# working.net
KiCad netlist of a schematic drawn in EAGLE
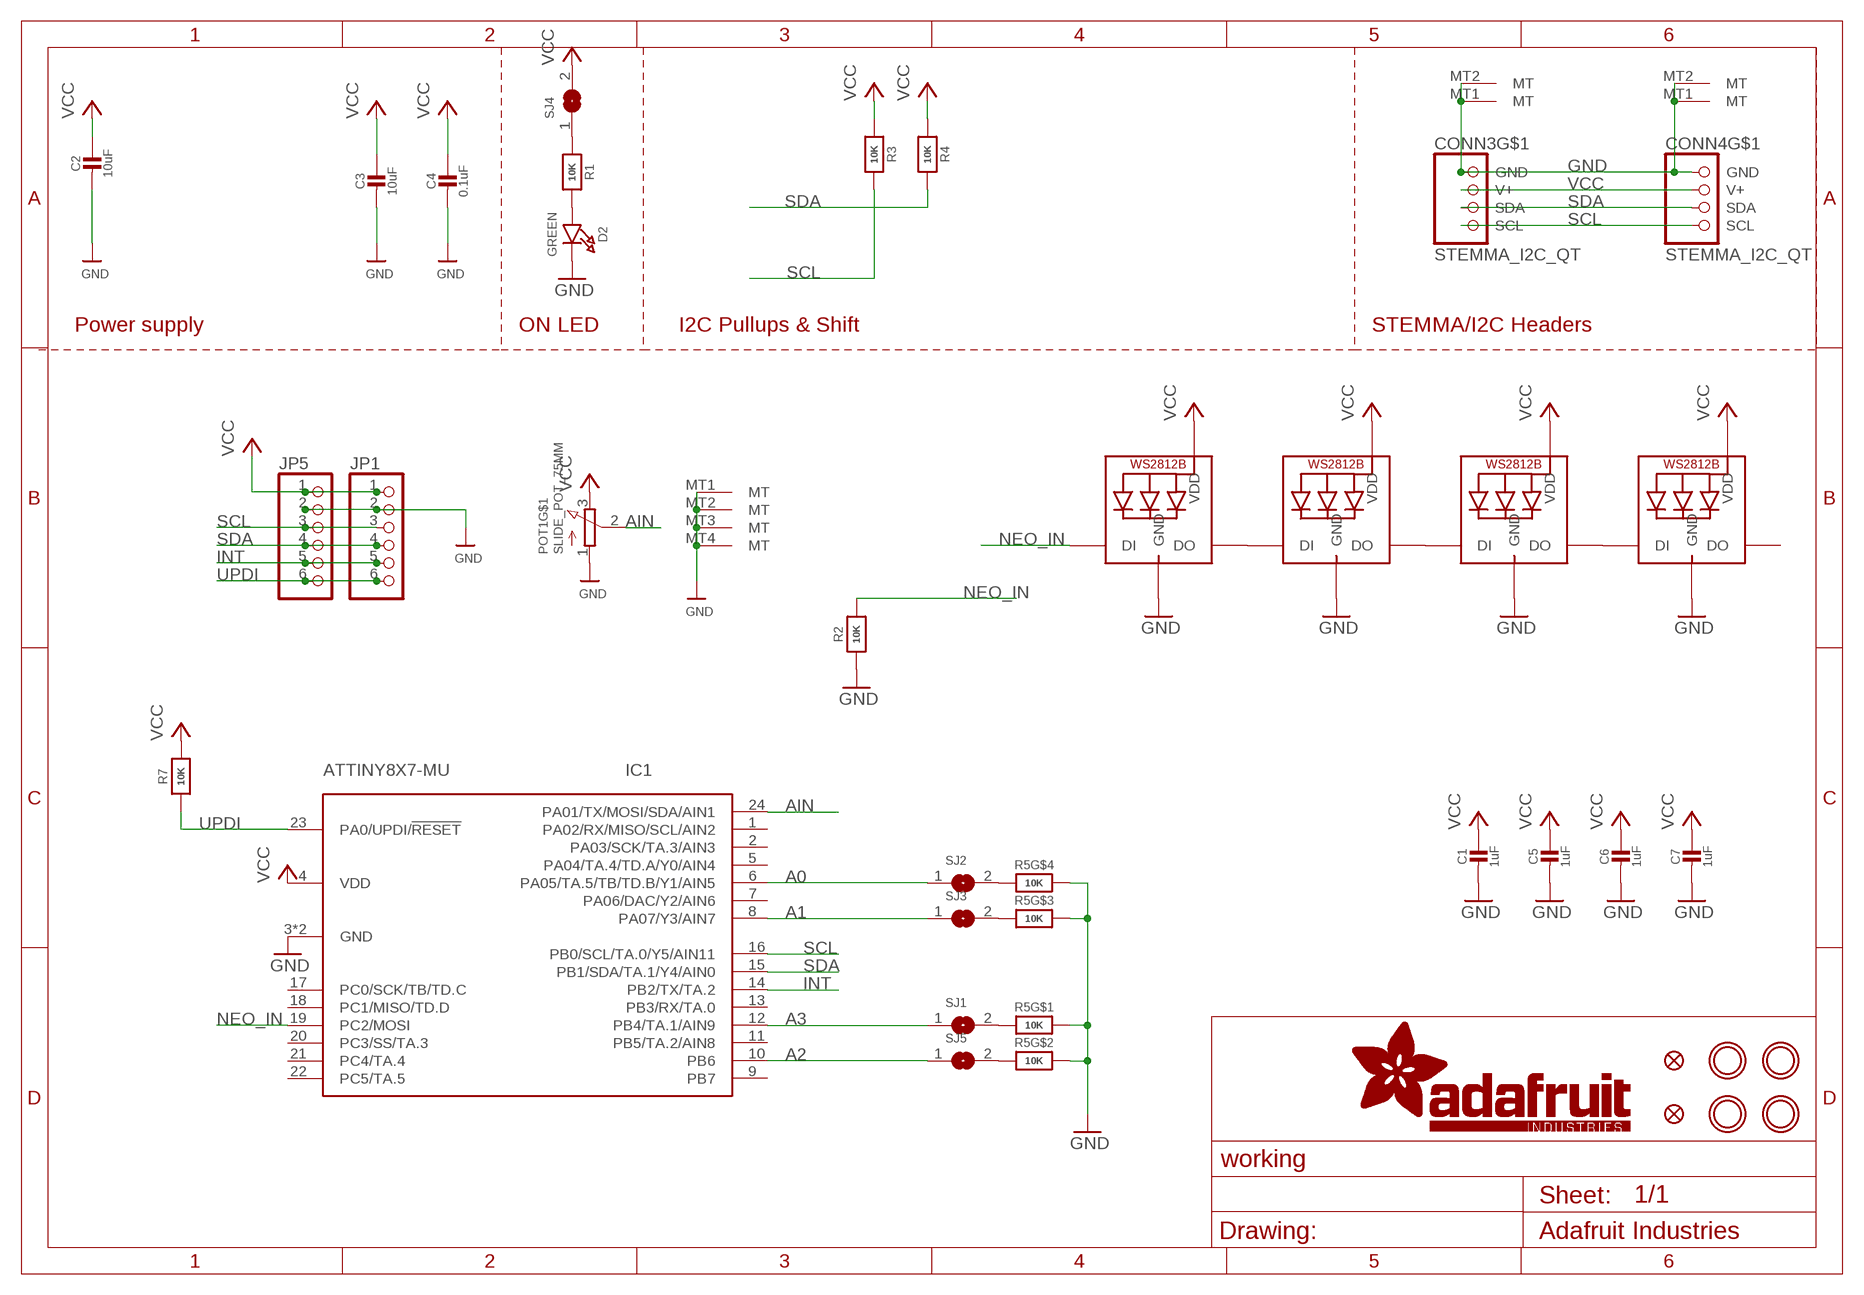
[diagram p0: schematic, sheet 1]

(export (version "E")
  (design (tool "Eeschema 10.0.6"))
  (components
    (comp (ref "C1")
      (value "1uF")
      (footprint "eagle-import:0603-NO")
      (libsource (lib "eagle-import") (part "CAP_CERAMIC0603_NO"))
    )
    (comp (ref "C2")
      (value "10uF")
      (footprint "eagle-import:0805-NO")
      (libsource (lib "eagle-import") (part "CAP_CERAMIC0805-NOOUTLINE"))
    )
    (comp (ref "C3")
      (value "10uF")
      (footprint "eagle-import:0805-NO")
      (libsource (lib "eagle-import") (part "CAP_CERAMIC0805-NOOUTLINE"))
    )
    (comp (ref "C4")
      (value "0.1uF")
      (footprint "eagle-import:0603-NO")
      (libsource (lib "eagle-import") (part "CAP_CERAMIC0603_NO"))
    )
    (comp (ref "C5")
      (value "1uF")
      (footprint "eagle-import:0603-NO")
      (libsource (lib "eagle-import") (part "CAP_CERAMIC0603_NO"))
    )
    (comp (ref "C6")
      (value "1uF")
      (footprint "eagle-import:0603-NO")
      (libsource (lib "eagle-import") (part "CAP_CERAMIC0603_NO"))
    )
    (comp (ref "C7")
      (value "1uF")
      (footprint "eagle-import:0603-NO")
      (libsource (lib "eagle-import") (part "CAP_CERAMIC0603_NO"))
    )
    (comp (ref "CONN3")
      (value "STEMMA_I2C_QT")
      (footprint "eagle-import:JST_SH4")
      (libsource (lib "eagle-import") (part "STEMMA_I2C_QT"))
    )
    (comp (ref "CONN4")
      (value "STEMMA_I2C_QT")
      (footprint "eagle-import:JST_SH4")
      (libsource (lib "eagle-import") (part "STEMMA_I2C_QT"))
    )
    (comp (ref "D2")
      (value "GREEN")
      (footprint "eagle-import:CHIPLED_0603_NOOUTLINE")
      (libsource (lib "eagle-import") (part "LED0603_NOOUTLINE"))
    )
    (comp (ref "FID1")
      (value "FIDUCIAL_1MM")
      (footprint "eagle-import:FIDUCIAL_1MM")
      (libsource (lib "eagle-import") (part "FIDUCIAL_1MM"))
    )
    (comp (ref "FID2")
      (value "FIDUCIAL_1MM")
      (footprint "eagle-import:FIDUCIAL_1MM")
      (libsource (lib "eagle-import") (part "FIDUCIAL_1MM"))
    )
    (comp (ref "IC1")
      (value "ATTINY8X7-MU")
      (footprint "eagle-import:QFN24_4MM")
      (libsource (lib "eagle-import") (part "ATTINY8X7-MU"))
    )
    (comp (ref "JP1")
      (value "HEADER-1X670MIL")
      (footprint "eagle-import:1X06_ROUND_70")
      (libsource (lib "eagle-import") (part "HEADER-1X670MIL"))
    )
    (comp (ref "JP5")
      (value "HEADER-1X670MIL")
      (footprint "eagle-import:1X06_ROUND_70")
      (libsource (lib "eagle-import") (part "HEADER-1X670MIL"))
    )
    (comp (ref "LED1")
      (value "WS2812B_SK6812E")
      (footprint "eagle-import:NEO3535_REVERSE")
      (libsource (lib "eagle-import") (part "WS2812B_SK6812E"))
    )
    (comp (ref "LED2")
      (value "WS2812B_SK6812E")
      (footprint "eagle-import:NEO3535_REVERSE")
      (libsource (lib "eagle-import") (part "WS2812B_SK6812E"))
    )
    (comp (ref "LED3")
      (value "WS2812B_SK6812E")
      (footprint "eagle-import:NEO3535_REVERSE")
      (libsource (lib "eagle-import") (part "WS2812B_SK6812E"))
    )
    (comp (ref "LED4")
      (value "WS2812B_SK6812E")
      (footprint "eagle-import:NEO3535_REVERSE")
      (libsource (lib "eagle-import") (part "WS2812B_SK6812E"))
    )
    (comp (ref "POT1")
      (value "SLIDE_POT_75MM")
      (footprint "eagle-import:SLIDE_POT_75MM")
      (libsource (lib "eagle-import") (part "SLIDE_POT_75MM"))
    )
    (comp (ref "R1")
      (value "10K")
      (footprint "eagle-import:0603-NO")
      (libsource (lib "eagle-import") (part "RESISTOR_0603_NOOUT"))
    )
    (comp (ref "R2")
      (value "10K")
      (footprint "eagle-import:0603-NO")
      (libsource (lib "eagle-import") (part "RESISTOR_0603_NOOUT"))
    )
    (comp (ref "R3")
      (value "10K")
      (footprint "eagle-import:0603-NO")
      (libsource (lib "eagle-import") (part "RESISTOR_0603_NOOUT"))
    )
    (comp (ref "R4")
      (value "10K")
      (footprint "eagle-import:0603-NO")
      (libsource (lib "eagle-import") (part "RESISTOR_0603_NOOUT"))
    )
    (comp (ref "R5")
      (value "10K")
      (footprint "eagle-import:RESPACK_4X0603")
      (libsource (lib "eagle-import") (part "RESISTOR_4PACK"))
    )
    (comp (ref "R7")
      (value "10K")
      (footprint "eagle-import:0603-NO")
      (libsource (lib "eagle-import") (part "RESISTOR_0603_NOOUT"))
    )
    (comp (ref "SJ1")
      (value "SOLDERJUMPERCLOSED")
      (footprint "eagle-import:SOLDERJUMPER_CLOSEDWIRE")
      (libsource (lib "eagle-import") (part "SOLDERJUMPERCLOSED"))
    )
    (comp (ref "SJ2")
      (value "SOLDERJUMPERCLOSED")
      (footprint "eagle-import:SOLDERJUMPER_CLOSEDWIRE")
      (libsource (lib "eagle-import") (part "SOLDERJUMPERCLOSED"))
    )
    (comp (ref "SJ3")
      (value "SOLDERJUMPERCLOSED")
      (footprint "eagle-import:SOLDERJUMPER_CLOSEDWIRE")
      (libsource (lib "eagle-import") (part "SOLDERJUMPERCLOSED"))
    )
    (comp (ref "SJ4")
      (value "SOLDERJUMPERCLOSED")
      (footprint "eagle-import:SOLDERJUMPER_CLOSEDWIRE")
      (libsource (lib "eagle-import") (part "SOLDERJUMPERCLOSED"))
    )
    (comp (ref "SJ5")
      (value "SOLDERJUMPERCLOSED")
      (footprint "eagle-import:SOLDERJUMPER_CLOSEDWIRE")
      (libsource (lib "eagle-import") (part "SOLDERJUMPERCLOSED"))
    )
    (comp (ref "U$3")
      (value "MOUNTINGHOLE2.5")
      (footprint "eagle-import:MOUNTINGHOLE_2.5_PLATED")
      (libsource (lib "eagle-import") (part "MOUNTINGHOLE2.5"))
    )
    (comp (ref "U$17")
      (value "MOUNTINGHOLE2.5")
      (footprint "eagle-import:MOUNTINGHOLE_2.5_PLATED")
      (libsource (lib "eagle-import") (part "MOUNTINGHOLE2.5"))
    )
    (comp (ref "U$19")
      (value "MOUNTINGHOLE2.5")
      (footprint "eagle-import:MOUNTINGHOLE_2.5_PLATED")
      (libsource (lib "eagle-import") (part "MOUNTINGHOLE2.5"))
    )
    (comp (ref "U$21")
      (value "MOUNTINGHOLE2.5")
      (footprint "eagle-import:MOUNTINGHOLE_2.5_PLATED")
      (libsource (lib "eagle-import") (part "MOUNTINGHOLE2.5"))
    )
  )
  (nets
    (net (code "1") (name "/A0") (class "Default")
      (node (ref "IC1") (pin "6") (pinfunction "PA05/TA.5/TB/TD.B/Y1/AIN5_6") (pintype "bidirectional"))
      (node (ref "SJ2") (pin "1") (pinfunction "1_1") (pintype "passive"))
    )
    (net (code "2") (name "/A1") (class "Default")
      (node (ref "IC1") (pin "8") (pinfunction "PA07/Y3/AIN7_8") (pintype "bidirectional"))
      (node (ref "SJ3") (pin "1") (pinfunction "1_1") (pintype "passive"))
    )
    (net (code "3") (name "/A2") (class "Default")
      (node (ref "IC1") (pin "10") (pinfunction "PB6_10") (pintype "bidirectional"))
      (node (ref "SJ5") (pin "1") (pinfunction "1_1") (pintype "passive"))
    )
    (net (code "4") (name "/A3") (class "Default")
      (node (ref "IC1") (pin "12") (pinfunction "PB4/TA.1/AIN9_12") (pintype "bidirectional"))
      (node (ref "SJ1") (pin "1") (pinfunction "1_1") (pintype "passive"))
    )
    (net (code "5") (name "/AIN") (class "Default")
      (node (ref "IC1") (pin "24") (pinfunction "PA01/TX/MOSI/SDA/AIN1_24") (pintype "bidirectional"))
      (node (ref "POT1") (pin "2") (pinfunction "S_2") (pintype "passive"))
    )
    (net (code "6") (name "/INT") (class "Default")
      (node (ref "IC1") (pin "14") (pinfunction "PB2/TX/TA.2_14") (pintype "bidirectional"))
      (node (ref "JP1") (pin "5") (pinfunction "5_5") (pintype "passive"))
      (node (ref "JP5") (pin "5") (pinfunction "5_5") (pintype "passive"))
    )
    (net (code "7") (name "/NEO_IN") (class "Default")
      (node (ref "IC1") (pin "19") (pinfunction "PC2/MOSI_19") (pintype "bidirectional"))
      (node (ref "LED1") (pin "4-DIN") (pinfunction "DI_4-DIN") (pintype "input"))
      (node (ref "R2") (pin "2") (pinfunction "2_2") (pintype "passive"))
    )
    (net (code "8") (name "/SCL") (class "Default")
      (node (ref "CONN3") (pin "4") (pinfunction "SCL_4") (pintype "passive"))
      (node (ref "CONN4") (pin "4") (pinfunction "SCL_4") (pintype "passive"))
      (node (ref "IC1") (pin "16") (pinfunction "PB0/SCL/TA.0/Y5/AIN11_16") (pintype "bidirectional"))
      (node (ref "JP1") (pin "3") (pinfunction "3_3") (pintype "passive"))
      (node (ref "JP5") (pin "3") (pinfunction "3_3") (pintype "passive"))
      (node (ref "R3") (pin "2") (pinfunction "2_2") (pintype "passive"))
    )
    (net (code "9") (name "/SDA") (class "Default")
      (node (ref "CONN3") (pin "3") (pinfunction "SDA_3") (pintype "passive"))
      (node (ref "CONN4") (pin "3") (pinfunction "SDA_3") (pintype "passive"))
      (node (ref "IC1") (pin "15") (pinfunction "PB1/SDA/TA.1/Y4/AIN0_15") (pintype "bidirectional"))
      (node (ref "JP1") (pin "4") (pinfunction "4_4") (pintype "passive"))
      (node (ref "JP5") (pin "4") (pinfunction "4_4") (pintype "passive"))
      (node (ref "R4") (pin "2") (pinfunction "2_2") (pintype "passive"))
    )
    (net (code "10") (name "/UPDI") (class "Default")
      (node (ref "IC1") (pin "23") (pinfunction "PA0/UPDI/~{RESET}_23") (pintype "bidirectional"))
      (node (ref "JP1") (pin "6") (pinfunction "6_6") (pintype "passive"))
      (node (ref "JP5") (pin "6") (pinfunction "6_6") (pintype "passive"))
      (node (ref "R7") (pin "1") (pinfunction "1_1") (pintype "passive"))
    )
    (net (code "11") (name "GND") (class "Default")
      (node (ref "C1") (pin "2") (pinfunction "2_2") (pintype "passive"))
      (node (ref "C2") (pin "2") (pinfunction "2_2") (pintype "passive"))
      (node (ref "C3") (pin "2") (pinfunction "2_2") (pintype "passive"))
      (node (ref "C4") (pin "2") (pinfunction "2_2") (pintype "passive"))
      (node (ref "C5") (pin "2") (pinfunction "2_2") (pintype "passive"))
      (node (ref "C6") (pin "2") (pinfunction "2_2") (pintype "passive"))
      (node (ref "C7") (pin "2") (pinfunction "2_2") (pintype "passive"))
      (node (ref "CONN3") (pin "1") (pinfunction "GND_1") (pintype "passive"))
      (node (ref "CONN3") (pin "MT1") (pinfunction "MT_MT1") (pintype "bidirectional"))
      (node (ref "CONN3") (pin "MT2") (pinfunction "MT_MT2") (pintype "bidirectional"))
      (node (ref "CONN4") (pin "1") (pinfunction "GND_1") (pintype "passive"))
      (node (ref "CONN4") (pin "MT1") (pinfunction "MT_MT1") (pintype "bidirectional"))
      (node (ref "CONN4") (pin "MT2") (pinfunction "MT_MT2") (pintype "bidirectional"))
      (node (ref "D2") (pin "C") (pinfunction "C_C") (pintype "passive"))
      (node (ref "IC1") (pin "3") (pinfunction "GND_3") (pintype "power_in"))
      (node (ref "IC1") (pin "THERM") (pinfunction "GND_THERM") (pintype "power_in"))
      (node (ref "JP1") (pin "2") (pinfunction "2_2") (pintype "passive"))
      (node (ref "JP5") (pin "2") (pinfunction "2_2") (pintype "passive"))
      (node (ref "LED1") (pin "3-GND") (pinfunction "GND_3-GND") (pintype "power_in"))
      (node (ref "LED2") (pin "3-GND") (pinfunction "GND_3-GND") (pintype "power_in"))
      (node (ref "LED3") (pin "3-GND") (pinfunction "GND_3-GND") (pintype "power_in"))
      (node (ref "LED4") (pin "3-GND") (pinfunction "GND_3-GND") (pintype "power_in"))
      (node (ref "POT1") (pin "1") (pinfunction "A_1") (pintype "passive"))
      (node (ref "POT1") (pin "MT1") (pinfunction "MT_MT1") (pintype "bidirectional"))
      (node (ref "POT1") (pin "MT2") (pinfunction "MT_MT2") (pintype "bidirectional"))
      (node (ref "POT1") (pin "MT3") (pinfunction "MT_MT3") (pintype "bidirectional"))
      (node (ref "POT1") (pin "MT4") (pinfunction "MT_MT4") (pintype "bidirectional"))
      (node (ref "R2") (pin "1") (pinfunction "1_1") (pintype "passive"))
      (node (ref "R5") (pin "5") (pinfunction "2_5") (pintype "passive"))
      (node (ref "R5") (pin "6") (pinfunction "2_6") (pintype "passive"))
      (node (ref "R5") (pin "7") (pinfunction "2_7") (pintype "passive"))
      (node (ref "R5") (pin "8") (pinfunction "2_8") (pintype "passive"))
    )
    (net (code "12") (name "Net-(D2-PadA)") (class "Default")
      (node (ref "D2") (pin "A") (pinfunction "A_A") (pintype "passive"))
      (node (ref "R1") (pin "2") (pinfunction "2_2") (pintype "passive"))
    )
    (net (code "13") (name "Net-(LED1-DO)") (class "Default")
      (node (ref "LED1") (pin "2-DOUT") (pinfunction "DO_2-DOUT") (pintype "output"))
      (node (ref "LED2") (pin "4-DIN") (pinfunction "DI_4-DIN") (pintype "input"))
    )
    (net (code "14") (name "Net-(LED2-DO)") (class "Default")
      (node (ref "LED2") (pin "2-DOUT") (pinfunction "DO_2-DOUT") (pintype "output"))
      (node (ref "LED3") (pin "4-DIN") (pinfunction "DI_4-DIN") (pintype "input"))
    )
    (net (code "15") (name "Net-(LED3-DO)") (class "Default")
      (node (ref "LED3") (pin "2-DOUT") (pinfunction "DO_2-DOUT") (pintype "output"))
      (node (ref "LED4") (pin "4-DIN") (pinfunction "DI_4-DIN") (pintype "input"))
    )
    (net (code "16") (name "Net-(R1-Pad1)") (class "Default")
      (node (ref "R1") (pin "1") (pinfunction "1_1") (pintype "passive"))
      (node (ref "SJ4") (pin "1") (pinfunction "1_1") (pintype "passive"))
    )
    (net (code "17") (name "Net-(R5-Pad1)") (class "Default")
      (node (ref "R5") (pin "1") (pinfunction "1_1") (pintype "passive"))
      (node (ref "SJ1") (pin "2") (pinfunction "2_2") (pintype "passive"))
    )
    (net (code "18") (name "Net-(R5B-1)") (class "Default")
      (node (ref "R5") (pin "2") (pinfunction "1_2") (pintype "passive"))
      (node (ref "SJ5") (pin "2") (pinfunction "2_2") (pintype "passive"))
    )
    (net (code "19") (name "Net-(R5C-1)") (class "Default")
      (node (ref "R5") (pin "3") (pinfunction "1_3") (pintype "passive"))
      (node (ref "SJ3") (pin "2") (pinfunction "2_2") (pintype "passive"))
    )
    (net (code "20") (name "Net-(R5D-1)") (class "Default")
      (node (ref "R5") (pin "4") (pinfunction "1_4") (pintype "passive"))
      (node (ref "SJ2") (pin "2") (pinfunction "2_2") (pintype "passive"))
    )
    (net (code "21") (name "VCC") (class "Default")
      (node (ref "C1") (pin "1") (pinfunction "1_1") (pintype "passive"))
      (node (ref "C2") (pin "1") (pinfunction "1_1") (pintype "passive"))
      (node (ref "C3") (pin "1") (pinfunction "1_1") (pintype "passive"))
      (node (ref "C4") (pin "1") (pinfunction "1_1") (pintype "passive"))
      (node (ref "C5") (pin "1") (pinfunction "1_1") (pintype "passive"))
      (node (ref "C6") (pin "1") (pinfunction "1_1") (pintype "passive"))
      (node (ref "C7") (pin "1") (pinfunction "1_1") (pintype "passive"))
      (node (ref "CONN3") (pin "2") (pinfunction "V+_2") (pintype "passive"))
      (node (ref "CONN4") (pin "2") (pinfunction "V+_2") (pintype "passive"))
      (node (ref "IC1") (pin "4") (pinfunction "VDD_4") (pintype "power_in"))
      (node (ref "JP1") (pin "1") (pinfunction "1_1") (pintype "passive"))
      (node (ref "JP5") (pin "1") (pinfunction "1_1") (pintype "passive"))
      (node (ref "LED1") (pin "1-VDD") (pinfunction "VDD_1-VDD") (pintype "power_in"))
      (node (ref "LED2") (pin "1-VDD") (pinfunction "VDD_1-VDD") (pintype "power_in"))
      (node (ref "LED3") (pin "1-VDD") (pinfunction "VDD_1-VDD") (pintype "power_in"))
      (node (ref "LED4") (pin "1-VDD") (pinfunction "VDD_1-VDD") (pintype "power_in"))
      (node (ref "POT1") (pin "3") (pinfunction "E_3") (pintype "passive"))
      (node (ref "R3") (pin "1") (pinfunction "1_1") (pintype "passive"))
      (node (ref "R4") (pin "1") (pinfunction "1_1") (pintype "passive"))
      (node (ref "R7") (pin "2") (pinfunction "2_2") (pintype "passive"))
      (node (ref "SJ4") (pin "2") (pinfunction "2_2") (pintype "passive"))
    )
    (net (code "22") (name "unconnected-(IC1-PA02{slash}RX{slash}MISO{slash}SCL{slash}AIN2-Pad1)") (class "Default")
      (node (ref "IC1") (pin "1") (pinfunction "PA02/RX/MISO/SCL/AIN2_1") (pintype "bidirectional"))
    )
    (net (code "23") (name "unconnected-(IC1-PA03{slash}SCK{slash}TA.3{slash}AIN3-Pad2)") (class "Default")
      (node (ref "IC1") (pin "2") (pinfunction "PA03/SCK/TA.3/AIN3_2") (pintype "bidirectional"))
    )
    (net (code "24") (name "unconnected-(IC1-PA04{slash}TA.4{slash}TD.A{slash}Y0{slash}AIN4-Pad5)") (class "Default")
      (node (ref "IC1") (pin "5") (pinfunction "PA04/TA.4/TD.A/Y0/AIN4_5") (pintype "bidirectional"))
    )
    (net (code "25") (name "unconnected-(IC1-PA06{slash}DAC{slash}Y2{slash}AIN6-Pad7)") (class "Default")
      (node (ref "IC1") (pin "7") (pinfunction "PA06/DAC/Y2/AIN6_7") (pintype "bidirectional"))
    )
    (net (code "26") (name "unconnected-(IC1-PB3{slash}RX{slash}TA.0-Pad13)") (class "Default")
      (node (ref "IC1") (pin "13") (pinfunction "PB3/RX/TA.0_13") (pintype "bidirectional"))
    )
    (net (code "27") (name "unconnected-(IC1-PB5{slash}TA.2{slash}AIN8-Pad11)") (class "Default")
      (node (ref "IC1") (pin "11") (pinfunction "PB5/TA.2/AIN8_11") (pintype "bidirectional"))
    )
    (net (code "28") (name "unconnected-(IC1-PB7-Pad9)") (class "Default")
      (node (ref "IC1") (pin "9") (pinfunction "PB7_9") (pintype "bidirectional"))
    )
    (net (code "29") (name "unconnected-(IC1-PC0{slash}SCK{slash}TB{slash}TD.C-Pad17)") (class "Default")
      (node (ref "IC1") (pin "17") (pinfunction "PC0/SCK/TB/TD.C_17") (pintype "bidirectional"))
    )
    (net (code "30") (name "unconnected-(IC1-PC1{slash}MISO{slash}TD.D-Pad18)") (class "Default")
      (node (ref "IC1") (pin "18") (pinfunction "PC1/MISO/TD.D_18") (pintype "bidirectional"))
    )
    (net (code "31") (name "unconnected-(IC1-PC3{slash}SS{slash}TA.3-Pad20)") (class "Default")
      (node (ref "IC1") (pin "20") (pinfunction "PC3/SS/TA.3_20") (pintype "bidirectional"))
    )
    (net (code "32") (name "unconnected-(IC1-PC4{slash}TA.4-Pad21)") (class "Default")
      (node (ref "IC1") (pin "21") (pinfunction "PC4/TA.4_21") (pintype "bidirectional"))
    )
    (net (code "33") (name "unconnected-(IC1-PC5{slash}TA.5-Pad22)") (class "Default")
      (node (ref "IC1") (pin "22") (pinfunction "PC5/TA.5_22") (pintype "bidirectional"))
    )
    (net (code "34") (name "unconnected-(LED4-DO-Pad2-DOUT)") (class "Default")
      (node (ref "LED4") (pin "2-DOUT") (pinfunction "DO_2-DOUT") (pintype "output"))
    )
  )
)
